# Test_Points.net
KiCad netlist of a schematic drawn in Altium Designer
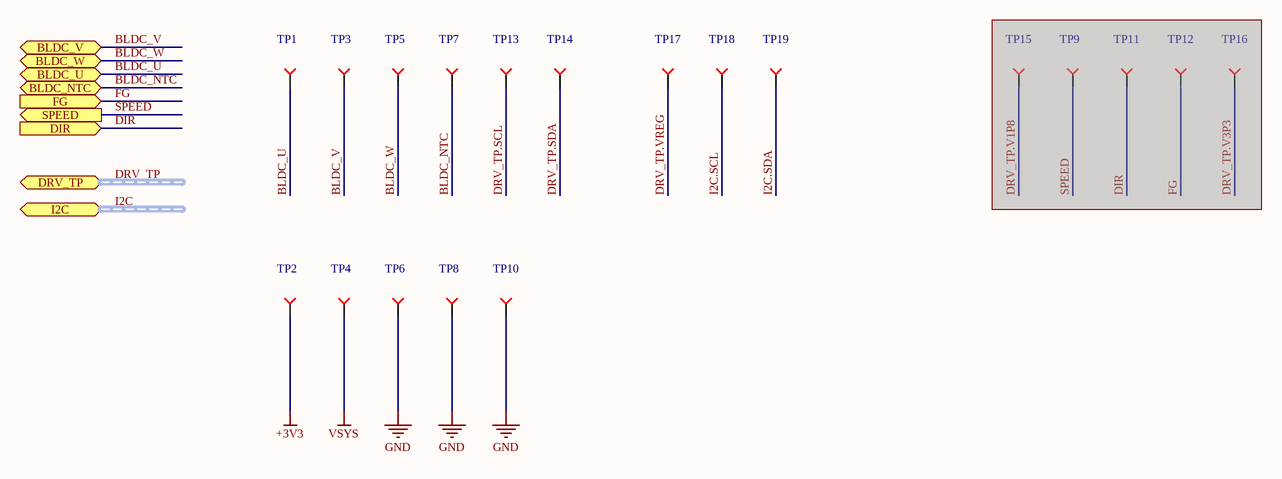
[diagram p0: Test_Points.SchDoc]

(export (version "E")
  (design (tool "Eeschema 10.0.6"))
  (components
    (comp (ref "TP1")
      (value "Test Point Pad")
      (footprint "Testpoint")
      (description "Test Point. There is nothing to buy or mount.")
      (libsource (lib "BLDC_Motor_Driver") (part "Test Point Pad"))
    )
    (comp (ref "TP2")
      (value "Test Point Pad")
      (footprint "Testpoint")
      (description "Test Point. There is nothing to buy or mount.")
      (libsource (lib "BLDC_Motor_Driver") (part "Test Point Pad"))
    )
    (comp (ref "TP3")
      (value "Test Point Pad")
      (footprint "Testpoint")
      (description "Test Point. There is nothing to buy or mount.")
      (libsource (lib "BLDC_Motor_Driver") (part "Test Point Pad"))
    )
    (comp (ref "TP4")
      (value "Test Point Pad")
      (footprint "Testpoint")
      (description "Test Point. There is nothing to buy or mount.")
      (libsource (lib "BLDC_Motor_Driver") (part "Test Point Pad"))
    )
    (comp (ref "TP5")
      (value "Test Point Pad")
      (footprint "Testpoint")
      (description "Test Point. There is nothing to buy or mount.")
      (libsource (lib "BLDC_Motor_Driver") (part "Test Point Pad"))
    )
    (comp (ref "TP6")
      (value "Test Point Pad")
      (footprint "Testpoint")
      (description "Test Point. There is nothing to buy or mount.")
      (libsource (lib "BLDC_Motor_Driver") (part "Test Point Pad"))
    )
    (comp (ref "TP7")
      (value "Test Point Pad")
      (footprint "Testpoint")
      (description "Test Point. There is nothing to buy or mount.")
      (libsource (lib "BLDC_Motor_Driver") (part "Test Point Pad"))
    )
    (comp (ref "TP8")
      (value "Test Point Pad")
      (footprint "Testpoint")
      (description "Test Point. There is nothing to buy or mount.")
      (libsource (lib "BLDC_Motor_Driver") (part "Test Point Pad"))
    )
    (comp (ref "TP9")
      (value "Test Point Pad")
      (footprint "Testpoint")
      (description "Test Point. There is nothing to buy or mount.")
      (libsource (lib "BLDC_Motor_Driver") (part "Test Point Pad"))
    )
    (comp (ref "TP10")
      (value "Test Point Pad")
      (footprint "Testpoint")
      (description "Test Point. There is nothing to buy or mount.")
      (libsource (lib "BLDC_Motor_Driver") (part "Test Point Pad"))
    )
    (comp (ref "TP11")
      (value "Test Point Pad")
      (footprint "Testpoint")
      (description "Test Point. There is nothing to buy or mount.")
      (libsource (lib "BLDC_Motor_Driver") (part "Test Point Pad"))
    )
    (comp (ref "TP12")
      (value "Test Point Pad")
      (footprint "Testpoint")
      (description "Test Point. There is nothing to buy or mount.")
      (libsource (lib "BLDC_Motor_Driver") (part "Test Point Pad"))
    )
    (comp (ref "TP13")
      (value "Test Point Pad")
      (footprint "Testpoint")
      (description "Test Point. There is nothing to buy or mount.")
      (libsource (lib "BLDC_Motor_Driver") (part "Test Point Pad"))
    )
    (comp (ref "TP14")
      (value "Test Point Pad")
      (footprint "Testpoint")
      (description "Test Point. There is nothing to buy or mount.")
      (libsource (lib "BLDC_Motor_Driver") (part "Test Point Pad"))
    )
    (comp (ref "TP15")
      (value "Test Point Pad")
      (footprint "Testpoint")
      (description "Test Point. There is nothing to buy or mount.")
      (libsource (lib "BLDC_Motor_Driver") (part "Test Point Pad"))
    )
    (comp (ref "TP16")
      (value "Test Point Pad")
      (footprint "Testpoint")
      (description "Test Point. There is nothing to buy or mount.")
      (libsource (lib "BLDC_Motor_Driver") (part "Test Point Pad"))
    )
    (comp (ref "TP17")
      (value "Test Point Pad")
      (footprint "Testpoint")
      (description "Test Point. There is nothing to buy or mount.")
      (libsource (lib "BLDC_Motor_Driver") (part "Test Point Pad"))
    )
    (comp (ref "TP18")
      (value "Test Point Pad")
      (footprint "Testpoint")
      (description "Test Point. There is nothing to buy or mount.")
      (libsource (lib "BLDC_Motor_Driver") (part "Test Point Pad"))
    )
    (comp (ref "TP19")
      (value "Test Point Pad")
      (footprint "Testpoint")
      (description "Test Point. There is nothing to buy or mount.")
      (libsource (lib "BLDC_Motor_Driver") (part "Test Point Pad"))
    )
  )
  (nets
    (net (code "3") (name "+3V3") (class "Default")
      (node (ref "TP2") (pin "1") (pinfunction "1_1") (pintype "passive"))
    )
    (net (code "4") (name "/BLDC_NTC") (class "Default")
      (node (ref "TP7") (pin "1") (pinfunction "1_1") (pintype "passive"))
    )
    (net (code "5") (name "/BLDC_U") (class "Default")
      (node (ref "TP1") (pin "1") (pinfunction "1_1") (pintype "passive"))
    )
    (net (code "6") (name "/BLDC_V") (class "Default")
      (node (ref "TP3") (pin "1") (pinfunction "1_1") (pintype "passive"))
    )
    (net (code "7") (name "/BLDC_W") (class "Default")
      (node (ref "TP5") (pin "1") (pinfunction "1_1") (pintype "passive"))
    )
    (net (code "8") (name "/DIR") (class "Default")
      (node (ref "TP11") (pin "1") (pinfunction "1_1") (pintype "passive"))
    )
    (net (code "9") (name "/DRV_TP.SCL") (class "Default")
      (node (ref "TP13") (pin "1") (pinfunction "1_1") (pintype "passive"))
    )
    (net (code "10") (name "/DRV_TP.SDA") (class "Default")
      (node (ref "TP14") (pin "1") (pinfunction "1_1") (pintype "passive"))
    )
    (net (code "11") (name "/DRV_TP.V1P8") (class "Default")
      (node (ref "TP15") (pin "1") (pinfunction "1_1") (pintype "passive"))
    )
    (net (code "12") (name "/DRV_TP.V3P3") (class "Default")
      (node (ref "TP16") (pin "1") (pinfunction "1_1") (pintype "passive"))
    )
    (net (code "13") (name "/DRV_TP.VREG") (class "Default")
      (node (ref "TP17") (pin "1") (pinfunction "1_1") (pintype "passive"))
    )
    (net (code "14") (name "/FG") (class "Default")
      (node (ref "TP12") (pin "1") (pinfunction "1_1") (pintype "passive"))
    )
    (net (code "15") (name "/I2C.SCL") (class "Default")
      (node (ref "TP18") (pin "1") (pinfunction "1_1") (pintype "passive"))
    )
    (net (code "16") (name "/I2C.SDA") (class "Default")
      (node (ref "TP19") (pin "1") (pinfunction "1_1") (pintype "passive"))
    )
    (net (code "17") (name "/SPEED") (class "Default")
      (node (ref "TP9") (pin "1") (pinfunction "1_1") (pintype "passive"))
    )
    (net (code "20") (name "GND") (class "Default")
      (node (ref "TP10") (pin "1") (pinfunction "1_1") (pintype "passive"))
      (node (ref "TP6") (pin "1") (pinfunction "1_1") (pintype "passive"))
      (node (ref "TP8") (pin "1") (pinfunction "1_1") (pintype "passive"))
    )
    (net (code "21") (name "VSYS") (class "Default")
      (node (ref "TP4") (pin "1") (pinfunction "1_1") (pintype "passive"))
    )
  )
)
